# TLV2361_breakout.net
KiCad netlist of a schematic drawn in EAGLE
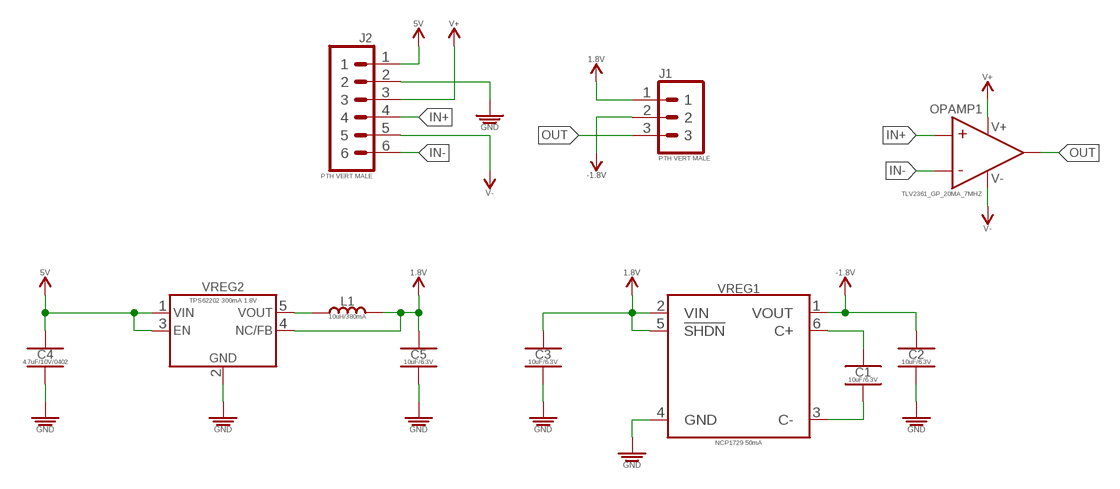
[diagram p0: schematic, sheet 1]

(export (version "E")
  (design (tool "Eeschema 10.0.6"))
  (components
    (comp (ref "C1")
      (value "10uF/6.3V")
      (footprint "eagle-import:CAPC1005X55_SMD-0402")
      (fields
        (field (name "MFR") "Murata Electronics North America")
        (field (name "MPN") "GRM155C80J106ME11D")
      )
      (libsource (lib "eagle-import") (part "10UF_CER_SMD-0402_6.3V-20%"))
    )
    (comp (ref "C2")
      (value "10uF/6.3V")
      (footprint "eagle-import:CAPC1005X55_SMD-0402")
      (fields
        (field (name "MFR") "Murata Electronics North America")
        (field (name "MPN") "GRM155C80J106ME11D")
      )
      (libsource (lib "eagle-import") (part "10UF_CER_SMD-0402_6.3V-20%"))
    )
    (comp (ref "C3")
      (value "10uF/6.3V")
      (footprint "eagle-import:CAPC1005X55_SMD-0402")
      (fields
        (field (name "MFR") "Murata Electronics North America")
        (field (name "MPN") "GRM155C80J106ME11D")
      )
      (libsource (lib "eagle-import") (part "10UF_CER_SMD-0402_6.3V-20%"))
    )
    (comp (ref "C4")
      (value "4.7uF/10V/0402")
      (footprint "eagle-import:CAPC1005X55_SMD-0402")
      (fields (field (name "MFR") "Samsung Electro-Mechanics") (field (name "MPN") "CL05A475MP5NRNC"))
      (libsource (lib "eagle-import") (part "4.7UF_CER_SMD-0402_10V-20%"))
    )
    (comp (ref "C5")
      (value "10uF/6.3V")
      (footprint "eagle-import:CAPC1005X55_SMD-0402")
      (fields
        (field (name "MFR") "Murata Electronics North America")
        (field (name "MPN") "GRM155C80J106ME11D")
      )
      (libsource (lib "eagle-import") (part "10UF_CER_SMD-0402_6.3V-20%"))
    )
    (comp (ref "J1")
      (value "PTH VERT MALE")
      (footprint "eagle-import:HDRV3W64P254_1X3_762X254X838B")
      (fields (field (name "MFR") "Sullins Connector Solutions") (field (name "MPN") "PEC03SAAN"))
      (libsource (lib "eagle-import") (part "1X03_PTH_VERT_MALE_2.54MM"))
    )
    (comp (ref "J2")
      (value "PTH VERT MALE")
      (footprint "eagle-import:HDRV6W64P254_1X6_1524X254X838B")
      (fields (field (name "MFR") "Sullins Connector Solutions") (field (name "MPN") "PEC06SAAN"))
      (libsource (lib "eagle-import") (part "1X06_PTH_VERT_MALE_2.54MM"))
    )
    (comp (ref "L1")
      (value "10uH/380mA")
      (footprint "eagle-import:INDC1608X60-0603")
      (fields (field (name "MFR") "Taiyo Yuden"))
      (libsource (lib "eagle-import") (part "10UH_SMD-0603_0.38A-0.468OHM-10%"))
    )
    (comp (ref "OPAMP1")
      (value "TLV2361_GP_20MA_7MHZ")
      (footprint "eagle-import:SOT95P280X145-5")
      (fields (field (name "MFR") "Texas Instruments") (field (name "MPN") "TLV2361IDBVR"))
      (libsource (lib "eagle-import") (part "TLV2361_GP_20MA_7MHZ"))
    )
    (comp (ref "VREG1")
      (value "NCP1729 50mA")
      (footprint "eagle-import:SOT95P275X100-6")
      (fields (field (name "MFR") "ON Semiconductor") (field (name "MPN") "NCV1729SN35T1G"))
      (libsource (lib "eagle-import") (part "VREG_NCP1729_NEGATIVE_SWITCHED-CAP-INVERTER_50MA"))
    )
    (comp (ref "VREG2")
      (value "TPS62202 300mA 1.8V")
      (footprint "eagle-import:SOT95P280X145-5")
      (fields (field (name "MFR") "Texas Instruments") (field (name "MPN") "TPS62202DBVR"))
      (libsource (lib "eagle-import") (part "VREG_SWITCHING_TPS6220XTPS62202_300MA_1.8V"))
    )
  )
  (nets
    (net (code "1") (name "-1.8V") (class "Default")
      (node (ref "C2") (pin "1") (pinfunction "1_1") (pintype "passive"))
      (node (ref "J1") (pin "2") (pinfunction "2_2") (pintype "passive"))
      (node (ref "VREG1") (pin "1") (pinfunction "VOUT_1") (pintype "bidirectional"))
    )
    (net (code "2") (name "1.8V") (class "Default")
      (node (ref "C3") (pin "1") (pinfunction "1_1") (pintype "passive"))
      (node (ref "C5") (pin "1") (pinfunction "1_1") (pintype "passive"))
      (node (ref "J1") (pin "1") (pinfunction "1_1") (pintype "passive"))
      (node (ref "L1") (pin "2") (pinfunction "2_2") (pintype "passive"))
      (node (ref "VREG1") (pin "2") (pinfunction "VIN_2") (pintype "bidirectional"))
      (node (ref "VREG1") (pin "5") (pinfunction "~{SHDN}_5") (pintype "bidirectional"))
      (node (ref "VREG2") (pin "4") (pinfunction "NC/FB_4") (pintype "bidirectional"))
    )
    (net (code "3") (name "5V") (class "Default")
      (node (ref "C4") (pin "1") (pinfunction "1_1") (pintype "passive"))
      (node (ref "J2") (pin "1") (pinfunction "1_1") (pintype "passive"))
      (node (ref "VREG2") (pin "1") (pinfunction "VIN_1") (pintype "power_in"))
      (node (ref "VREG2") (pin "3") (pinfunction "EN_3") (pintype "bidirectional"))
    )
    (net (code "4") (name "GND") (class "Default")
      (node (ref "C2") (pin "2") (pinfunction "2_2") (pintype "passive"))
      (node (ref "C3") (pin "2") (pinfunction "2_2") (pintype "passive"))
      (node (ref "C4") (pin "2") (pinfunction "2_2") (pintype "passive"))
      (node (ref "C5") (pin "2") (pinfunction "2_2") (pintype "passive"))
      (node (ref "J2") (pin "2") (pinfunction "2_2") (pintype "passive"))
      (node (ref "VREG1") (pin "4") (pinfunction "GND_4") (pintype "bidirectional"))
      (node (ref "VREG2") (pin "2") (pinfunction "GND_2") (pintype "power_in"))
    )
    (net (code "5") (name "IN+") (class "Default")
      (node (ref "J2") (pin "4") (pinfunction "4_4") (pintype "passive"))
      (node (ref "OPAMP1") (pin "1") (pinfunction "IN+_1") (pintype "input"))
    )
    (net (code "6") (name "IN-") (class "Default")
      (node (ref "J2") (pin "6") (pinfunction "6_6") (pintype "passive"))
      (node (ref "OPAMP1") (pin "3") (pinfunction "IN-_3") (pintype "input"))
    )
    (net (code "7") (name "Net-(VREG1-C+)") (class "Default")
      (node (ref "C1") (pin "1") (pinfunction "1_1") (pintype "passive"))
      (node (ref "VREG1") (pin "6") (pinfunction "C+_6") (pintype "bidirectional"))
    )
    (net (code "8") (name "Net-(VREG1-C-)") (class "Default")
      (node (ref "C1") (pin "2") (pinfunction "2_2") (pintype "passive"))
      (node (ref "VREG1") (pin "3") (pinfunction "C-_3") (pintype "bidirectional"))
    )
    (net (code "9") (name "Net-(VREG2-VOUT)") (class "Default")
      (node (ref "L1") (pin "1") (pinfunction "1_1") (pintype "passive"))
      (node (ref "VREG2") (pin "5") (pinfunction "VOUT_5") (pintype "power_in"))
    )
    (net (code "10") (name "OUT") (class "Default")
      (node (ref "J1") (pin "3") (pinfunction "3_3") (pintype "passive"))
      (node (ref "OPAMP1") (pin "4") (pinfunction "OUT_4") (pintype "output"))
    )
    (net (code "11") (name "V+") (class "Default")
      (node (ref "J2") (pin "3") (pinfunction "3_3") (pintype "passive"))
      (node (ref "OPAMP1") (pin "5") (pinfunction "V+_5") (pintype "passive"))
    )
    (net (code "12") (name "V-") (class "Default")
      (node (ref "J2") (pin "5") (pinfunction "5_5") (pintype "passive"))
      (node (ref "OPAMP1") (pin "2") (pinfunction "V-_2") (pintype "passive"))
    )
  )
)
